# 24Vto12V_2025-03-30_12-48-15.net
KiCad netlist of a schematic drawn in EasyEDA Pro
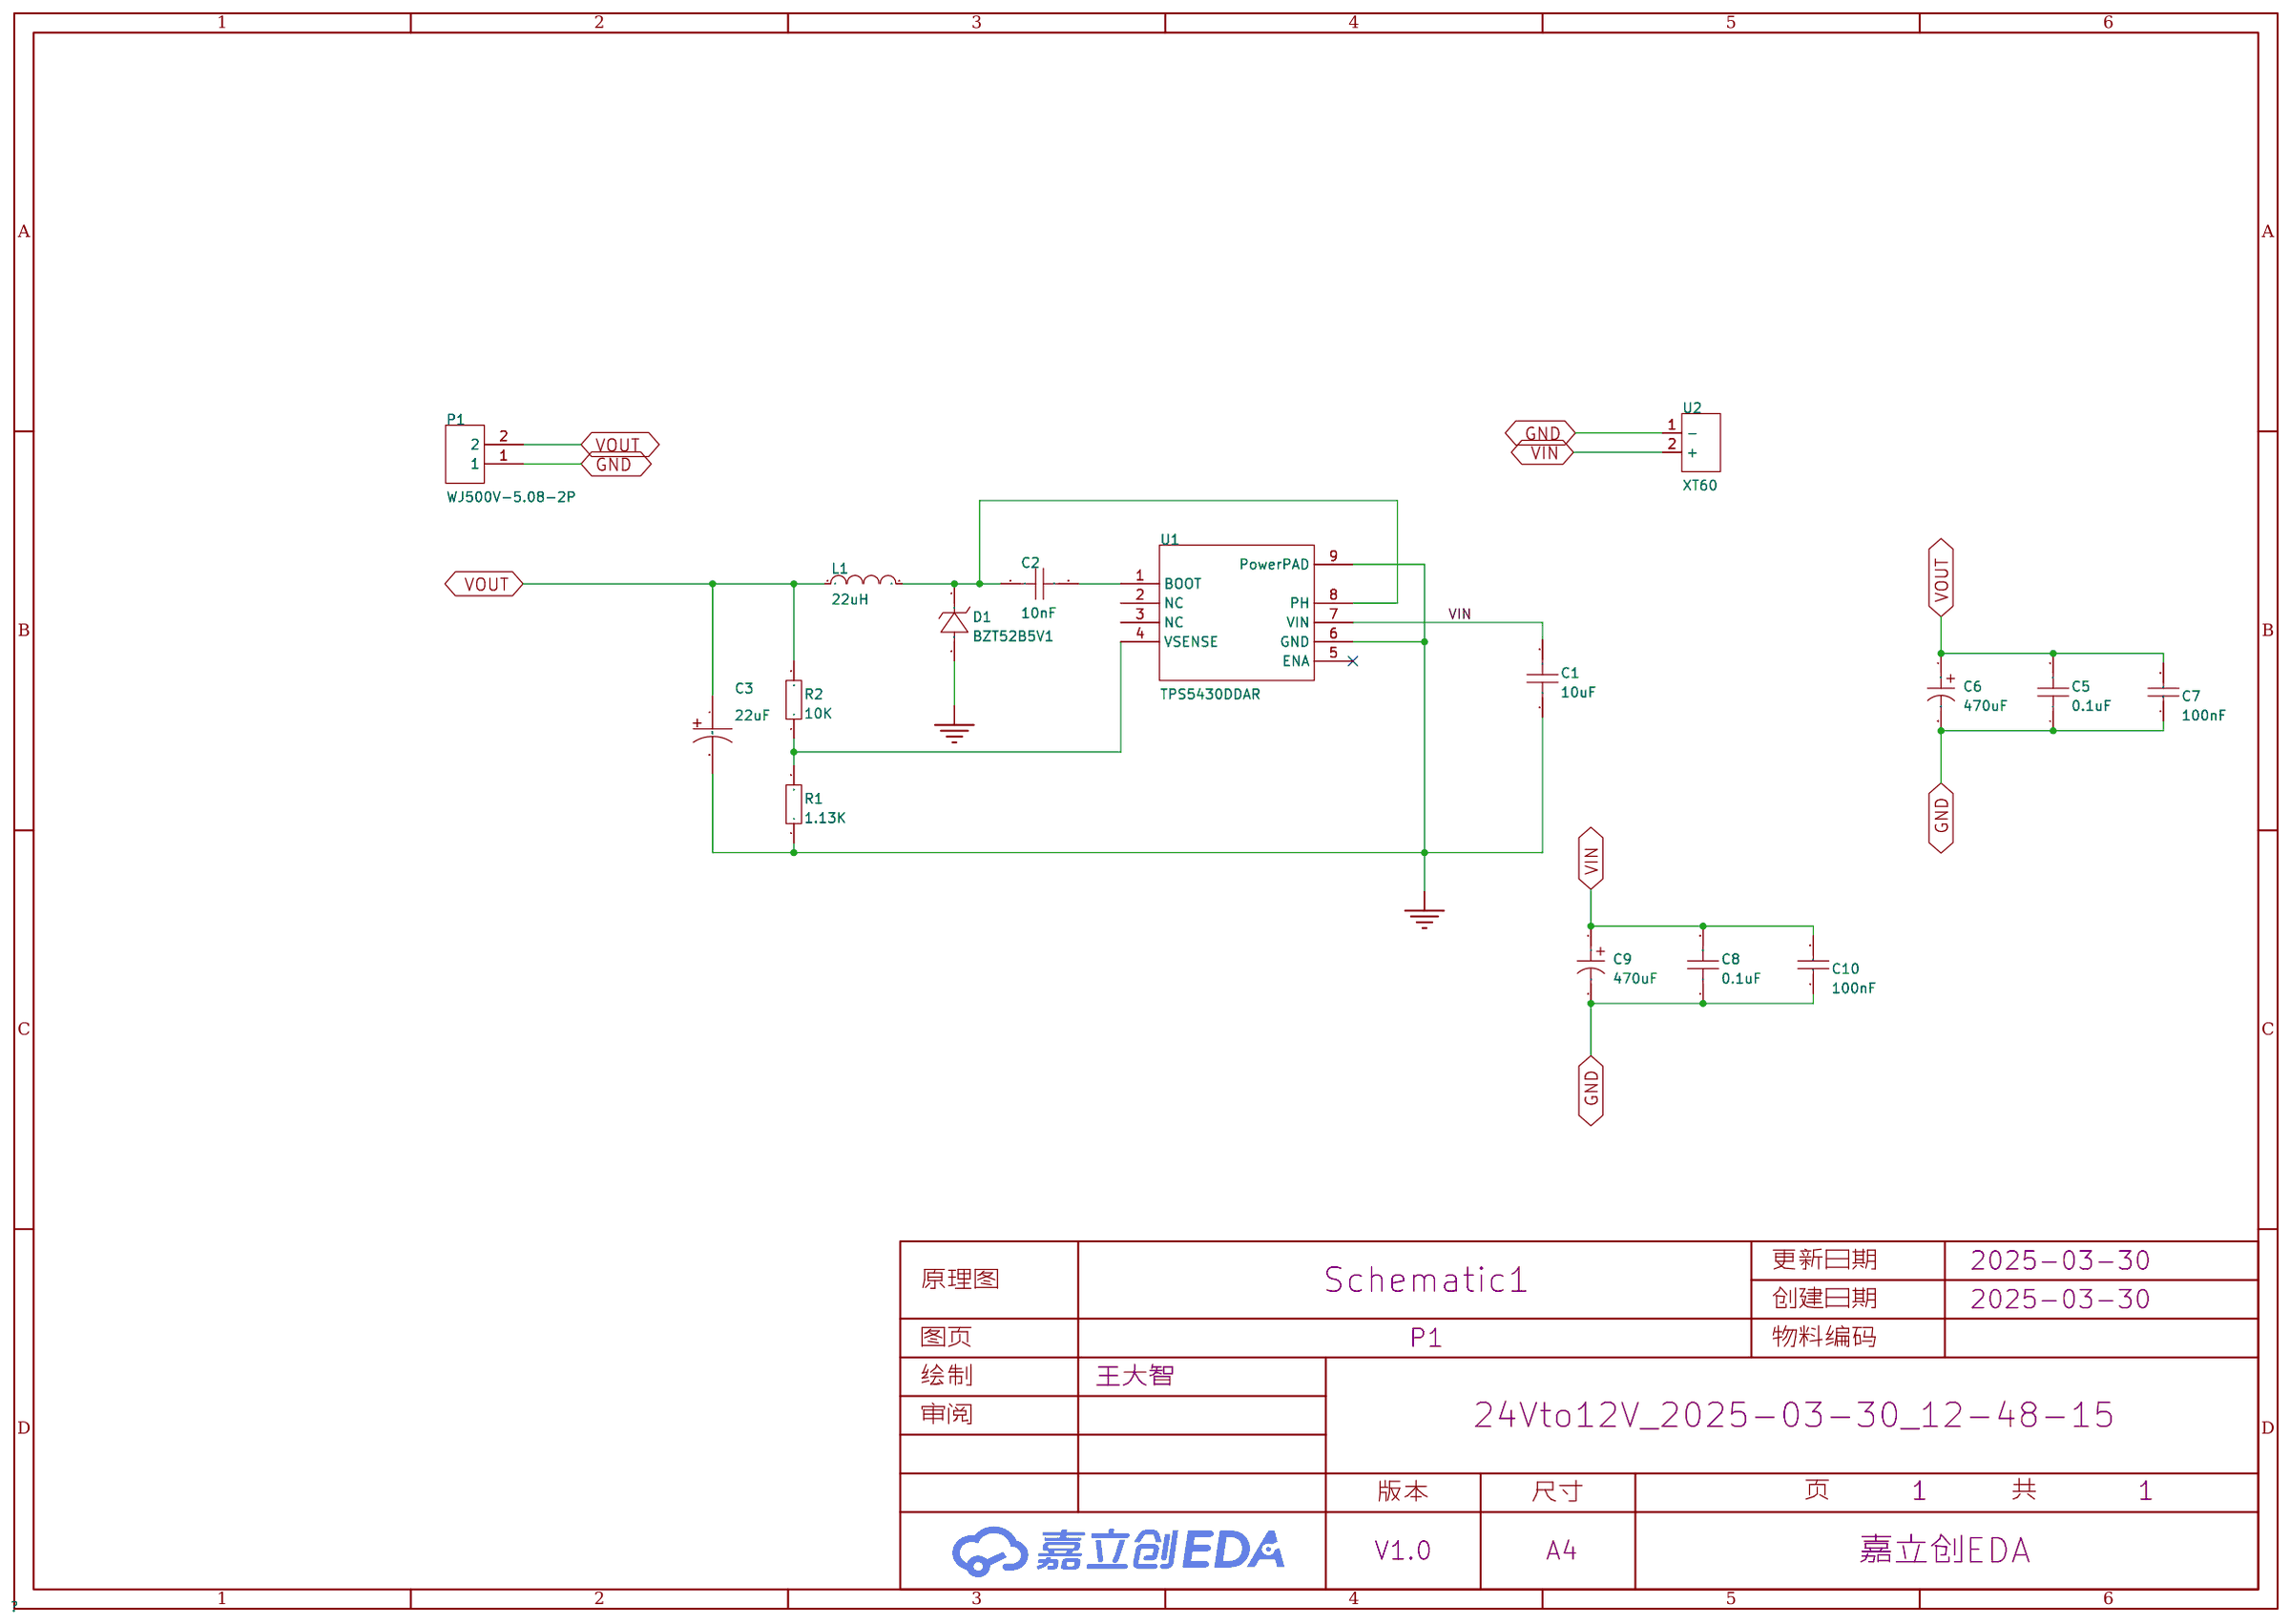
[diagram p0: schematic sheet]

(export (version "E")
  (design (tool "Eeschema 10.0.6"))
  (components
    (comp (ref "C1")
      (value "10uF")
      (footprint "easyedapro:C0603")
      (libsource (lib "easyedapro") (part "CapAcitance"))
    )
    (comp (ref "C2")
      (value "10nF")
      (footprint "easyedapro:C0603")
      (libsource (lib "easyedapro") (part "CapAcitance"))
    )
    (comp (ref "C3")
      (value "22uF")
      (footprint "easyedapro:CAP-SMD_L3.5-W2.8-R-RD")
      (description "容值:22uF;精度:±10%;额定电压:20V;等效串联电阻:400mΩ@100kHz;")
      (fields
        (field (name "Manufacturer Part") "TPSB226K020R0400")
        (field (name "Manufacturer") "Kyocera AVX")
      )
      (libsource (lib "easyedapro") (part "TPSB226K020R0400"))
    )
    (comp (ref "C5")
      (value "0.1uF")
      (footprint "easyedapro:C0603")
      (libsource (lib "easyedapro") (part "CapAcitance"))
    )
    (comp (ref "C6")
      (value "470uF")
      (footprint "easyedapro:CAP-TH_BD8.0-P3.50-D0.6-FD_1")
      (description "容值:470uF;额定电压:25V;")
      (fields
        (field (name "Manufacturer Part") "CD2884771EM0812VFL")
        (field (name "Manufacturer") "HRK(鸿瑞凯电子)")
      )
      (libsource (lib "easyedapro") (part "CD2884771EM0812VFL"))
    )
    (comp (ref "C7")
      (value "100nF")
      (footprint "easyedapro:CAP-TH_L8.5-W5.0-P5.00-D1.2")
      (description "容值:100nF;精度:±20%;额定电压:50V;温度系数:Y5V;")
      (fields (field (name "Manufacturer Part") "CT4-0805Y104M500F3") (field (name "Manufacturer") "FH(风华)"))
      (libsource (lib "easyedapro") (part "CT4-0805Y104M500F3"))
    )
    (comp (ref "C8")
      (value "0.1uF")
      (footprint "easyedapro:C0603")
      (libsource (lib "easyedapro") (part "CapAcitance"))
    )
    (comp (ref "C9")
      (value "470uF")
      (footprint "easyedapro:CAP-TH_BD8.0-P3.50-D0.6-FD_1")
      (description "容值:470uF;额定电压:25V;")
      (fields
        (field (name "Manufacturer Part") "CD2884771EM0812VFL")
        (field (name "Manufacturer") "HRK(鸿瑞凯电子)")
      )
      (libsource (lib "easyedapro") (part "CD2884771EM0812VFL"))
    )
    (comp (ref "C10")
      (value "100nF")
      (footprint "easyedapro:CAP-TH_L8.5-W5.0-P5.00-D1.2")
      (description "容值:100nF;精度:±20%;额定电压:50V;温度系数:Y5V;")
      (fields (field (name "Manufacturer Part") "CT4-0805Y104M500F3") (field (name "Manufacturer") "FH(风华)"))
      (libsource (lib "easyedapro") (part "CT4-0805Y104M500F3"))
    )
    (comp (ref "D1")
      (value "BZT52B5V1")
      (footprint "easyedapro:SOD-123_L2.7-W1.6-LS3.7-RD")
      (description "二极管配置:独立式;稳压值(标称值):5.1V;稳压值(范围):5V~5.2V;耗散功率(Pd):500mW;")
      (fields (field (name "Manufacturer") "宏嘉诚"))
      (libsource (lib "easyedapro") (part "BZT52B5V1_C19077393"))
    )
    (comp (ref "L1")
      (value "22uH")
      (footprint "easyedapro:L0603")
      (libsource (lib "easyedapro") (part "SDFL1608S100KTF"))
    )
    (comp (ref "P1")
      (value "WJ500V-5.08-2P")
      (footprint "easyedapro:CONN-TH_2P-P5.00_WJ500V-5.08-2P")
      (fields (field (name "Manufacturer") "KANGNEX(康奈克斯电气)"))
      (libsource (lib "easyedapro") (part "WJ500V-5.08-2P-14-00A"))
    )
    (comp (ref "R1")
      (value "1.13K")
      (footprint "easyedapro:R0603")
      (libsource (lib "easyedapro") (part "电阻"))
    )
    (comp (ref "R2") (value "10K") (footprint "easyedapro:R0603") (libsource (lib "easyedapro") (part "电阻")))
    (comp (ref "U1")
      (value "TPS5430DDAR")
      (footprint "easyedapro:ESOP-8_L4.9-W3.9-P1.27-LS6.0-TL-EP")
      (description "功能类型:降压型;输出类型:可调;工作电压:5.5V~36V;输出电压:1.221V~32.04V;输出电流:3A;")
      (fields (field (name "Manufacturer") "TI(德州仪器)"))
      (libsource (lib "easyedapro") (part "TPS5430DDAR"))
    )
    (comp (ref "U2")
      (value "XT60")
      (footprint "easyedapro:CONN-TH_XT60")
      (description "类别:-;类型1:-;")
      (fields (field (name "Manufacturer") "AMASS(艾迈斯)"))
      (libsource (lib "easyedapro") (part "XT60"))
    )
  )
  (nets
    (net (code "1") (name "GND") (class "Default")
      (node (ref "C1") (pin "1") (pinfunction "1_1") (pintype "input"))
      (node (ref "C10") (pin "1") (pinfunction "1_1") (pintype "input"))
      (node (ref "C3") (pin "2") (pinfunction "2_2") (pintype "unspecified"))
      (node (ref "C5") (pin "1") (pinfunction "1_1") (pintype "input"))
      (node (ref "C6") (pin "2") (pinfunction "2_2") (pintype "input"))
      (node (ref "C7") (pin "1") (pinfunction "1_1") (pintype "input"))
      (node (ref "C8") (pin "1") (pinfunction "1_1") (pintype "input"))
      (node (ref "C9") (pin "2") (pinfunction "2_2") (pintype "input"))
      (node (ref "D1") (pin "2") (pinfunction "A_2") (pintype "unspecified"))
      (node (ref "P1") (pin "1") (pinfunction "1_1") (pintype "unspecified"))
      (node (ref "R1") (pin "1") (pinfunction "1_1") (pintype "input"))
      (node (ref "U1") (pin "6") (pinfunction "GND_6") (pintype "unspecified"))
      (node (ref "U1") (pin "9") (pinfunction "PowerPAD_9") (pintype "unspecified"))
      (node (ref "U2") (pin "1") (pinfunction "-_1") (pintype "unspecified"))
    )
    (net (code "2") (name "Net-(D1-K)") (class "Default")
      (node (ref "C2") (pin "1") (pinfunction "1_1") (pintype "input"))
      (node (ref "D1") (pin "1") (pinfunction "K_1") (pintype "unspecified"))
      (node (ref "L1") (pin "2") (pinfunction "2_2") (pintype "unspecified"))
      (node (ref "U1") (pin "8") (pinfunction "PH_8") (pintype "unspecified"))
    )
    (net (code "3") (name "Net-(U1-BOOT)") (class "Default")
      (node (ref "C2") (pin "2") (pinfunction "2_2") (pintype "input"))
      (node (ref "U1") (pin "1") (pinfunction "BOOT_1") (pintype "unspecified"))
    )
    (net (code "4") (name "Net-(U1-VSENSE)") (class "Default")
      (node (ref "R1") (pin "2") (pinfunction "2_2") (pintype "input"))
      (node (ref "R2") (pin "1") (pinfunction "1_1") (pintype "input"))
      (node (ref "U1") (pin "4") (pinfunction "VSENSE_4") (pintype "unspecified"))
    )
    (net (code "5") (name "VIN") (class "Default")
      (node (ref "C1") (pin "2") (pinfunction "2_2") (pintype "input"))
      (node (ref "C10") (pin "2") (pinfunction "2_2") (pintype "input"))
      (node (ref "C8") (pin "2") (pinfunction "2_2") (pintype "input"))
      (node (ref "C9") (pin "1") (pinfunction "1_1") (pintype "input"))
      (node (ref "U1") (pin "7") (pinfunction "VIN_7") (pintype "unspecified"))
      (node (ref "U2") (pin "2") (pinfunction "+_2") (pintype "unspecified"))
    )
    (net (code "6") (name "VOUT") (class "Default")
      (node (ref "C3") (pin "1") (pinfunction "1_1") (pintype "unspecified"))
      (node (ref "C5") (pin "2") (pinfunction "2_2") (pintype "input"))
      (node (ref "C6") (pin "1") (pinfunction "1_1") (pintype "input"))
      (node (ref "C7") (pin "2") (pinfunction "2_2") (pintype "input"))
      (node (ref "L1") (pin "1") (pinfunction "1_1") (pintype "unspecified"))
      (node (ref "P1") (pin "2") (pinfunction "2_2") (pintype "unspecified"))
      (node (ref "R2") (pin "2") (pinfunction "2_2") (pintype "input"))
    )
    (net (code "7") (name "unconnected-(U1-ENA-Pad5)") (class "Default")
      (node (ref "U1") (pin "5") (pinfunction "ENA_5") (pintype "unspecified+no_connect"))
    )
    (net (code "8") (name "unconnected-(U1-NC-Pad2)") (class "Default")
      (node (ref "U1") (pin "2") (pinfunction "NC_2") (pintype "unspecified"))
    )
    (net (code "9") (name "unconnected-(U1-NC-Pad3)") (class "Default")
      (node (ref "U1") (pin "3") (pinfunction "NC_3") (pintype "unspecified"))
    )
  )
)
